# VREG_RT9166-18PVL.net
KiCad netlist of a schematic drawn in Altium Designer
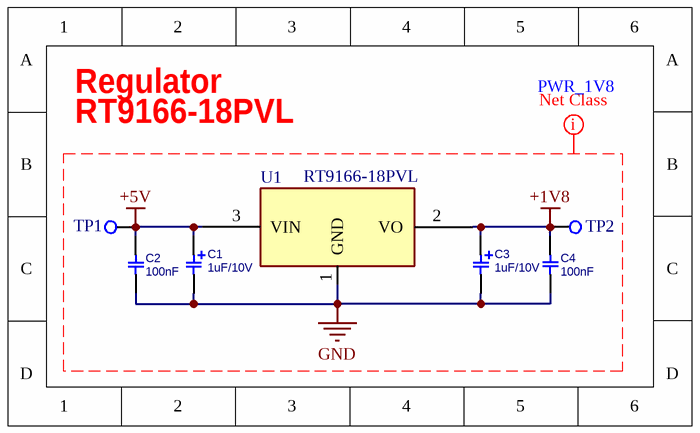
[diagram p0: VREG RT9166-18PVL.SchDoc]

(export (version "E")
  (design (tool "Eeschema 10.0.6"))
  (components
    (comp (ref "C1")
      (value "1uF/10V")
      (footprint "C_TN_A")
      (description "CAP, SMD, TAN")
      (libsource (lib "PW Components 97_492") (part "CAP_SMD_TAN"))
    )
    (comp (ref "C2")
      (value "100nF")
      (footprint "C0603S")
      (description "CAP, SMD, MLCC")
      (fields (field (name "MANF_P#") "MANF_PART#") (field (name "MANF") "Murata"))
      (libsource (lib "Passive") (part "CAP_SMD_MLCC"))
    )
    (comp (ref "C3")
      (value "1uF/10V")
      (footprint "C_TN_A")
      (description "CAP, SMD, TAN")
      (libsource (lib "PW Components 97_492") (part "CAP_SMD_TAN"))
    )
    (comp (ref "C4")
      (value "100nF")
      (footprint "C0603S")
      (description "CAP, SMD, MLCC")
      (fields (field (name "MANF_P#") "MANF_PART#") (field (name "MANF") "Murata"))
      (libsource (lib "Passive") (part "CAP_SMD_MLCC"))
    )
    (comp (ref "TP1")
      (value "Test Point")
      (footprint "TPSMD_C1")
      (libsource (lib "Passives") (part "Test Point"))
    )
    (comp (ref "TP2")
      (value "Test Point")
      (footprint "TPSMD_C1")
      (libsource (lib "Passives") (part "Test Point"))
    )
    (comp (ref "U1")
      (value "RT9166-18PVL")
      (footprint "SOT23_3")
      (description "REG, Linear, Fixed, 1.8v, 0.3A/0.6A, SOT23")
      (fields (field (name "MANF") "TI"))
      (libsource (lib "PW Components 97_472") (part "VREG_RT9166A-18PVL_SOT23"))
    )
  )
  (nets
    (net (code "1") (name "+1V8") (class "Default")
      (node (ref "C3") (pin "1") (pinfunction "1_1") (pintype "passive"))
      (node (ref "C4") (pin "1") (pinfunction "1_1") (pintype "passive"))
      (node (ref "TP2") (pin "1") (pinfunction "TP_1") (pintype "passive"))
      (node (ref "U1") (pin "2") (pinfunction "VO_2") (pintype "passive"))
    )
    (net (code "2") (name "+5V") (class "Default")
      (node (ref "C1") (pin "1") (pinfunction "1_1") (pintype "passive"))
      (node (ref "C2") (pin "1") (pinfunction "1_1") (pintype "passive"))
      (node (ref "TP1") (pin "1") (pinfunction "TP_1") (pintype "passive"))
      (node (ref "U1") (pin "3") (pinfunction "VIN_3") (pintype "passive"))
    )
    (net (code "3") (name "GND") (class "Default")
      (node (ref "C1") (pin "2") (pinfunction "2_2") (pintype "passive"))
      (node (ref "C2") (pin "2") (pinfunction "2_2") (pintype "passive"))
      (node (ref "C3") (pin "2") (pinfunction "2_2") (pintype "passive"))
      (node (ref "C4") (pin "2") (pinfunction "2_2") (pintype "passive"))
      (node (ref "U1") (pin "1") (pinfunction "GND_1") (pintype "passive"))
    )
  )
)
